# yarns_v03.net
KiCad netlist of a schematic drawn in EAGLE
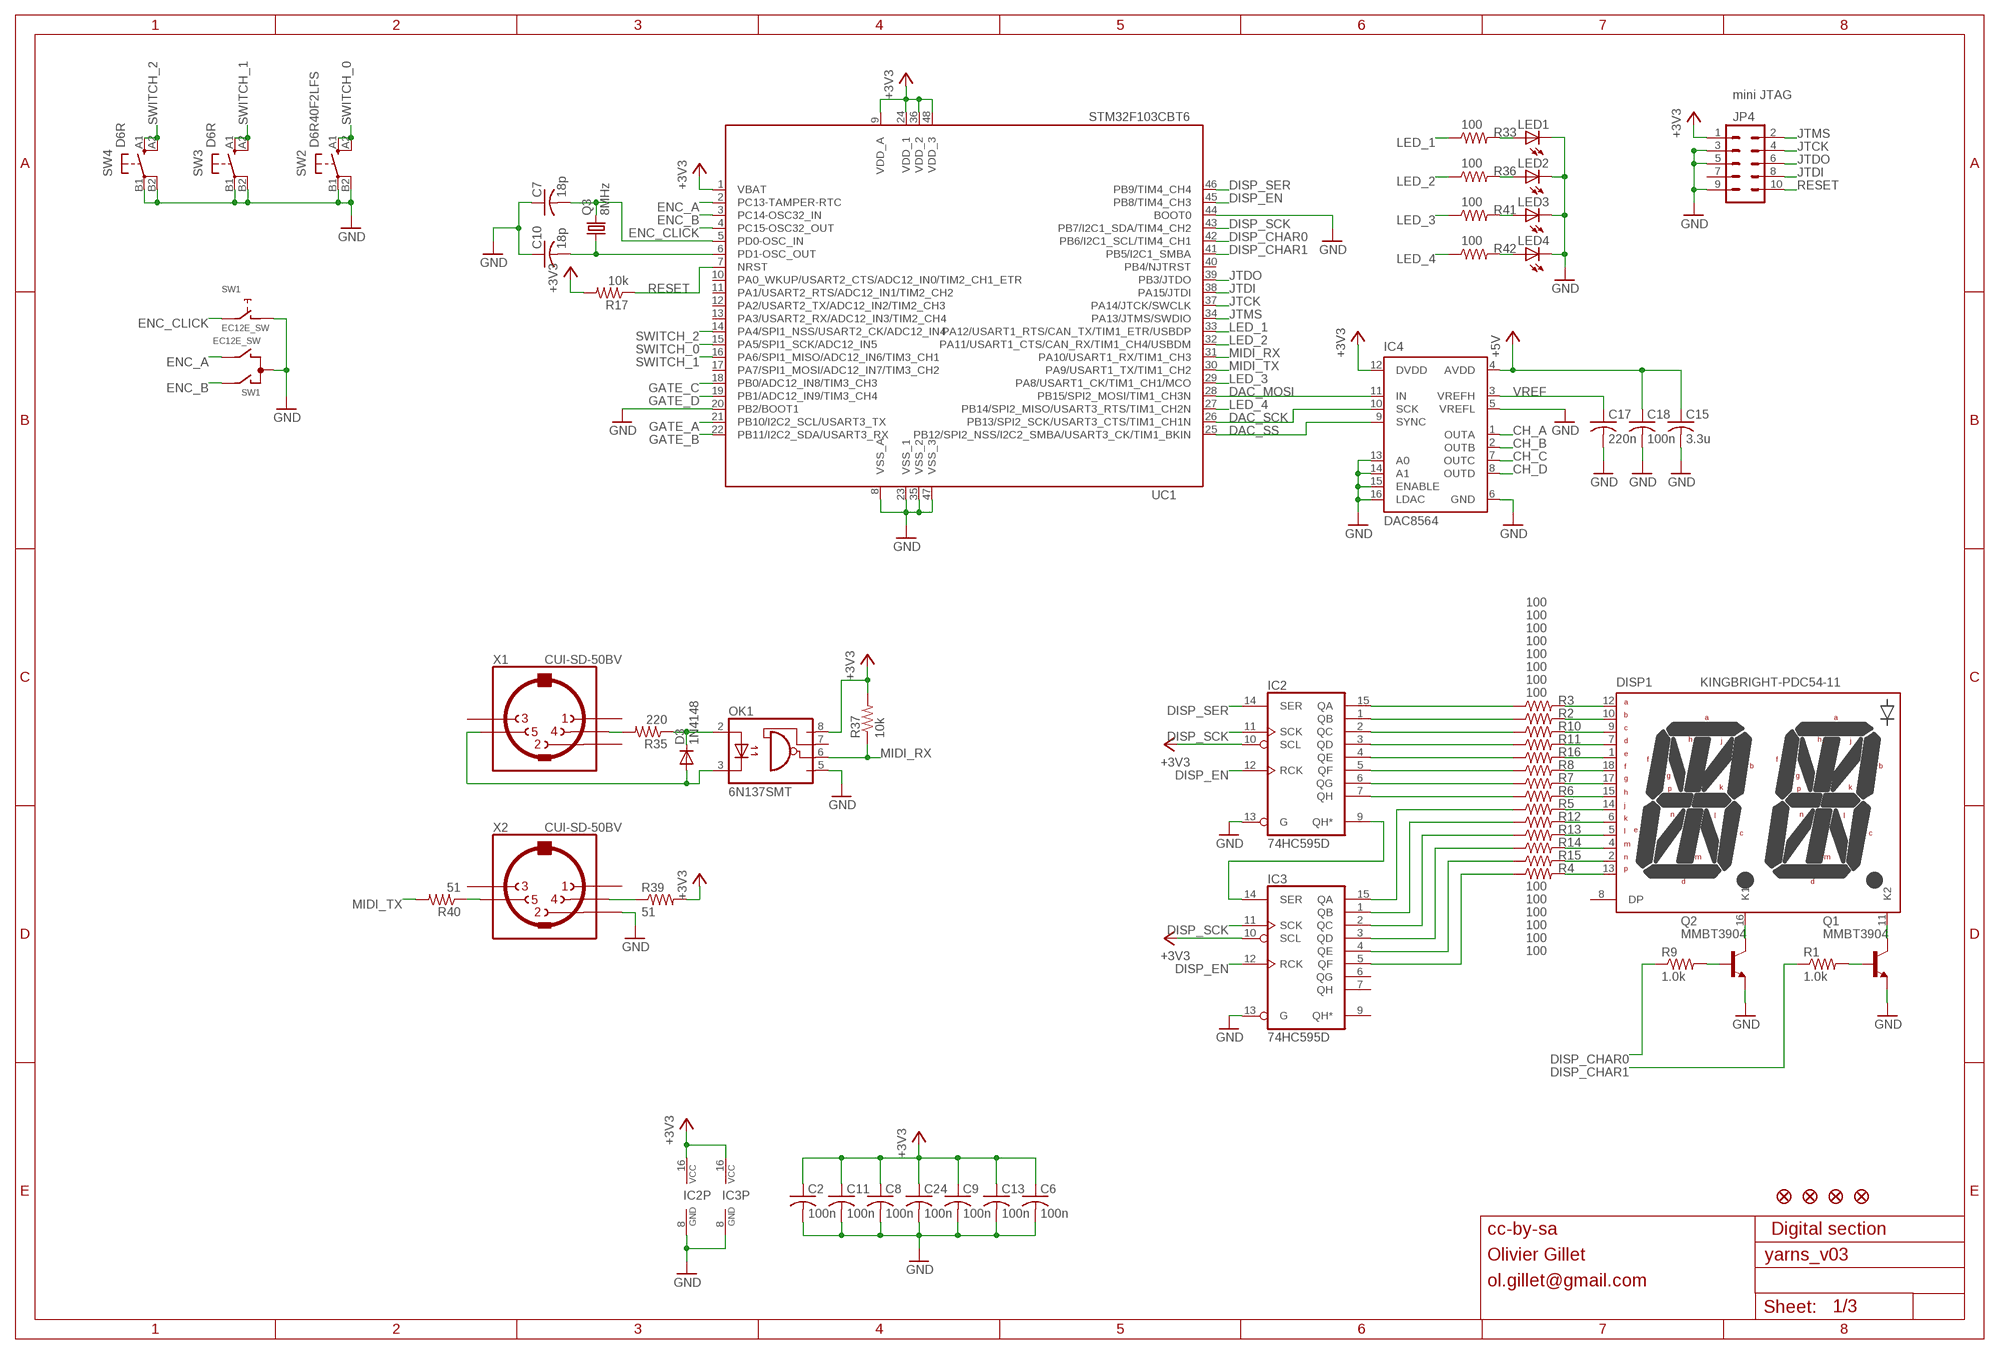
[diagram p0: schematic, sheet 1]
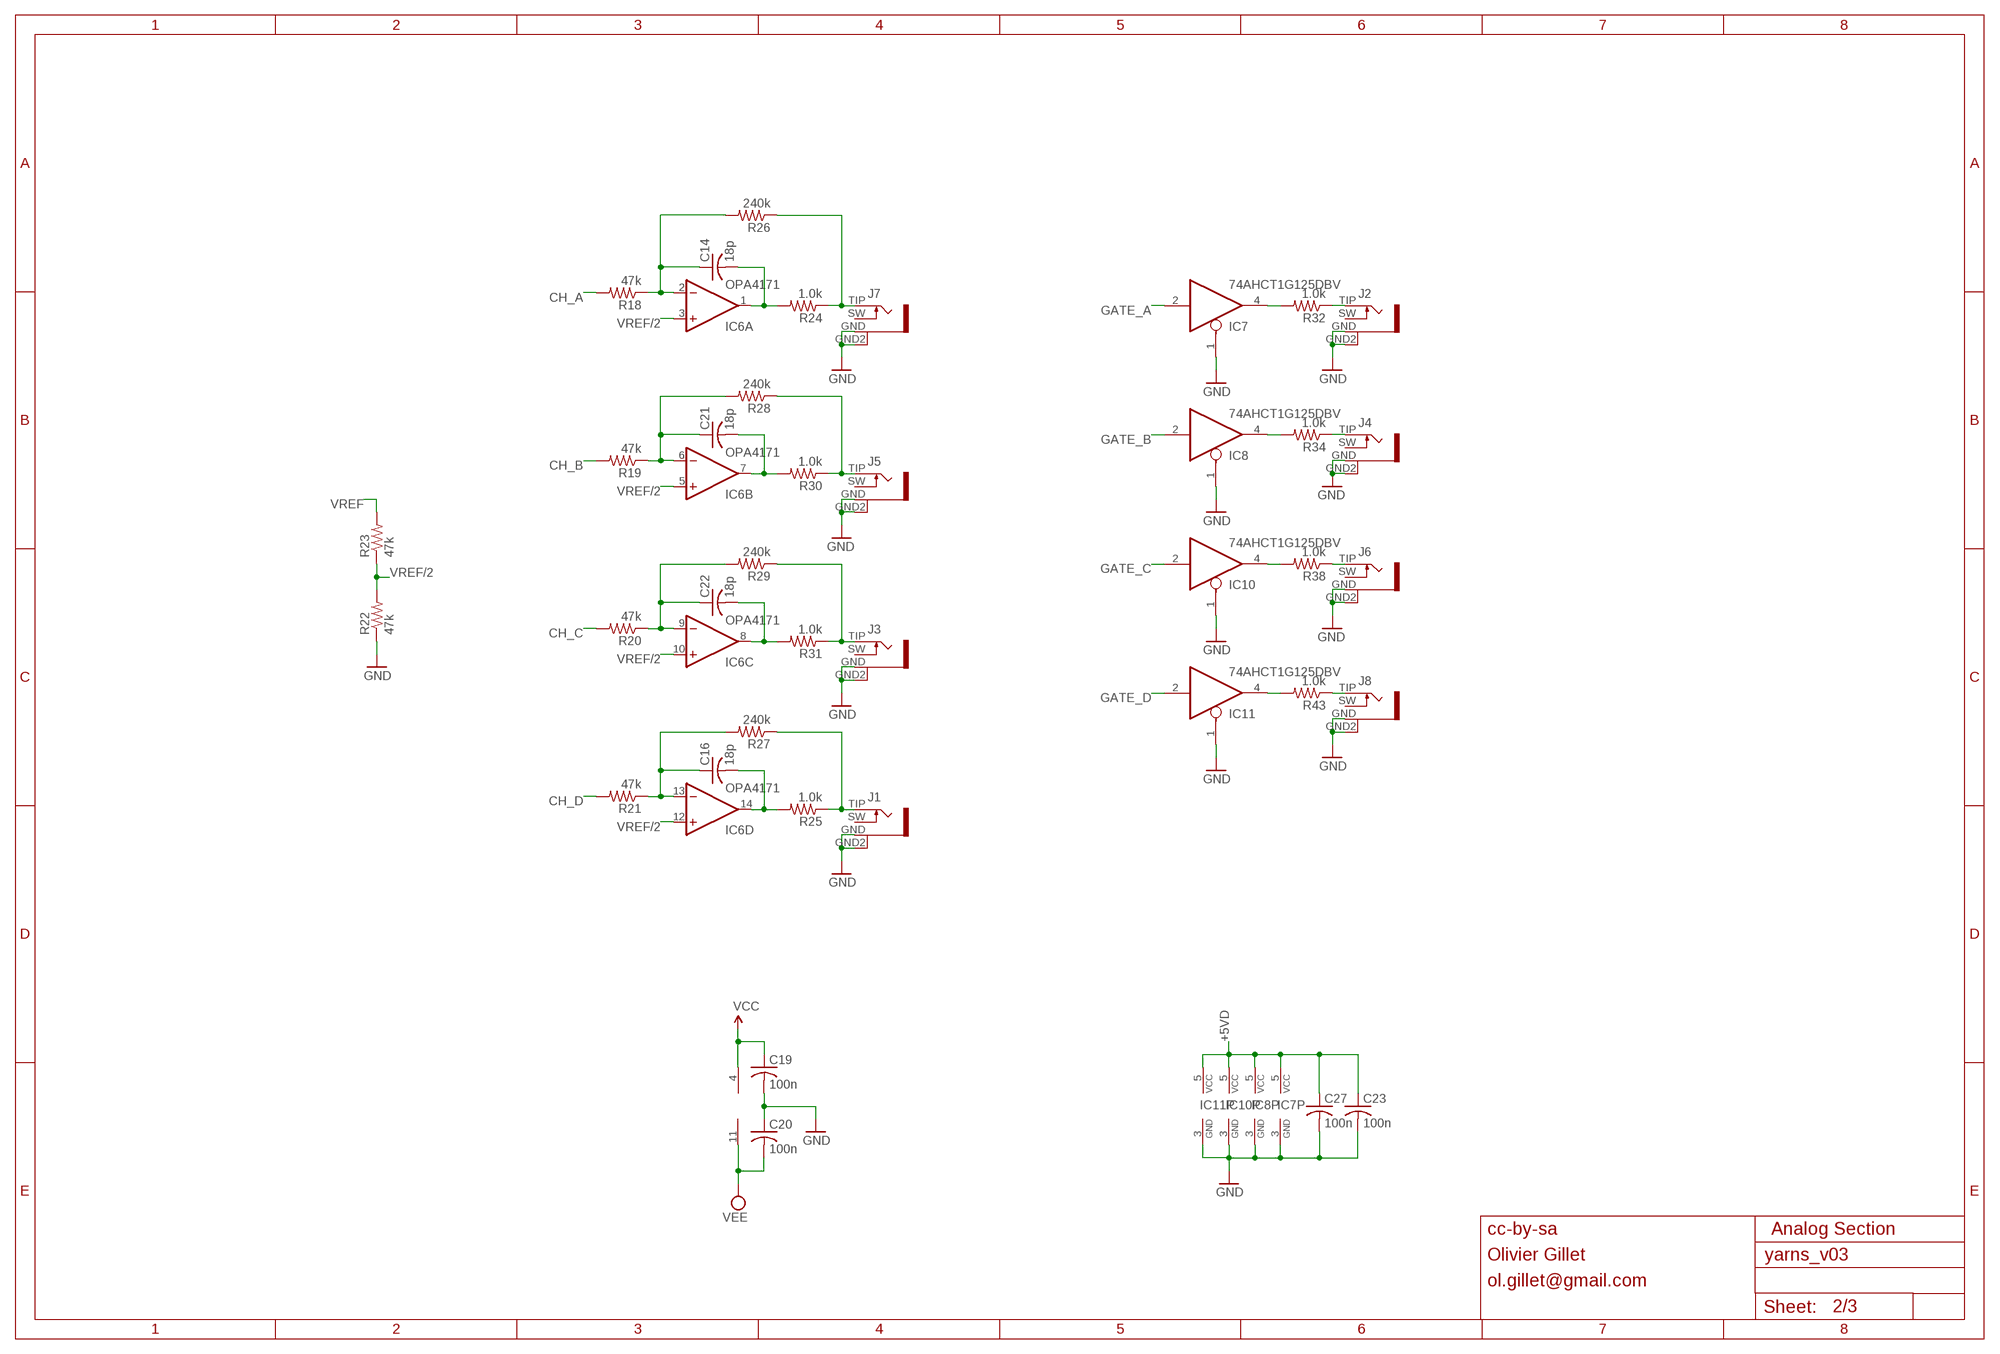
[diagram p1: schematic, sheet 2]
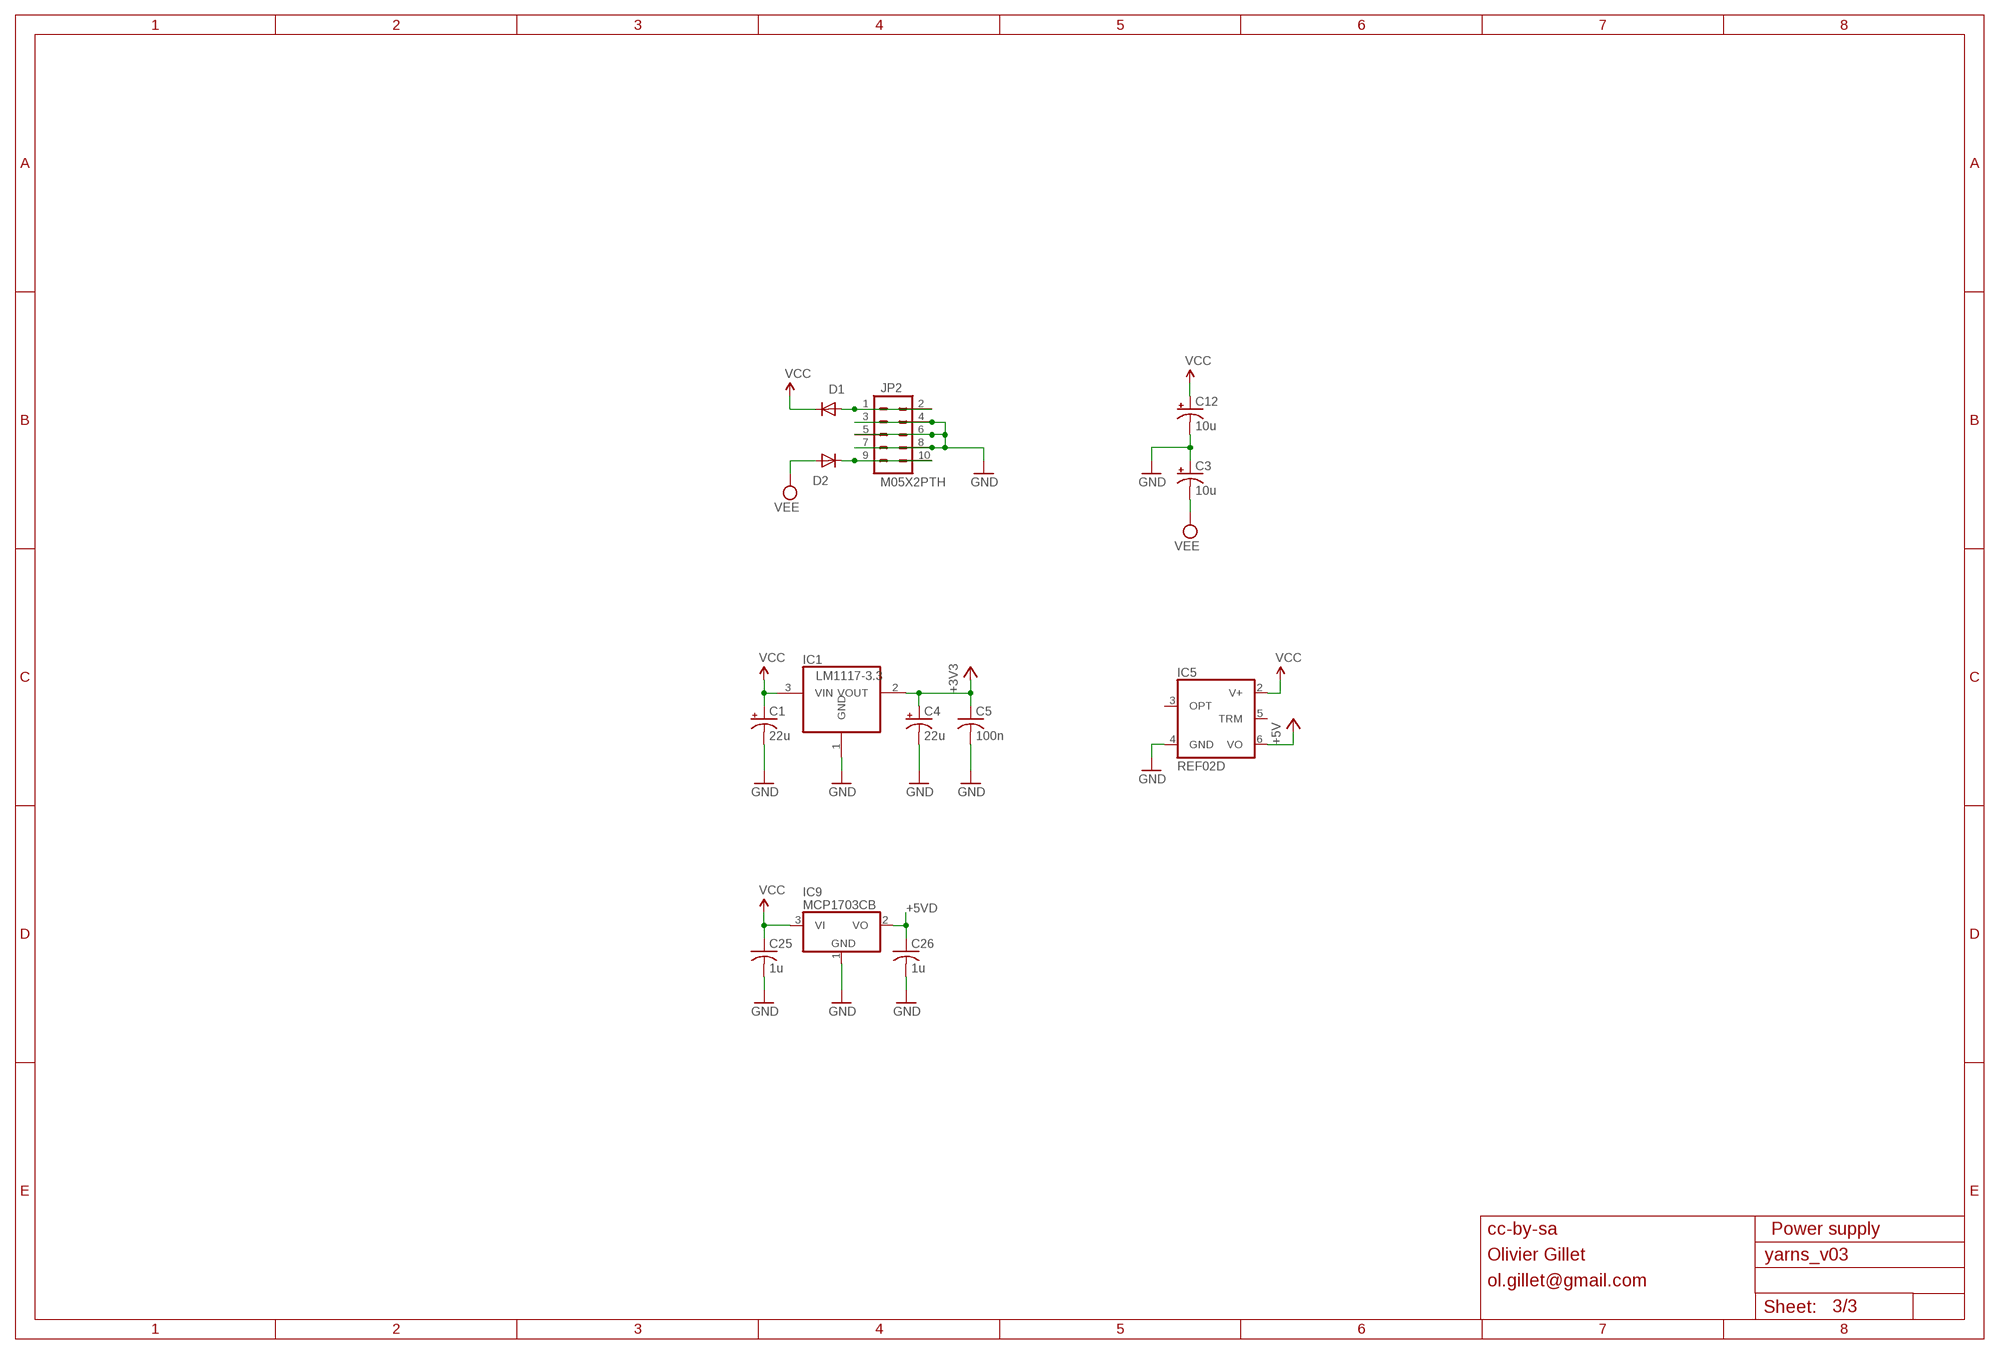
[diagram p2: schematic, sheet 3]

(export (version "E")
  (design (tool "Eeschema 10.0.6"))
  (components
    (comp (ref "C1")
      (value "22u")
      (footprint "eagle-import:PANASONIC_C")
      (libsource (lib "eagle-import") (part "CPOL-USC"))
    )
    (comp (ref "C3")
      (value "10u")
      (footprint "eagle-import:PANASONIC_A")
      (libsource (lib "eagle-import") (part "CPOL-USA"))
    )
    (comp (ref "C4")
      (value "22u")
      (footprint "eagle-import:PANASONIC_C")
      (libsource (lib "eagle-import") (part "CPOL-USC"))
    )
    (comp (ref "C5")
      (value "100n")
      (footprint "eagle-import:C0603")
      (libsource (lib "eagle-import") (part "C-USC0603"))
    )
    (comp (ref "C12")
      (value "10u")
      (footprint "eagle-import:PANASONIC_A")
      (libsource (lib "eagle-import") (part "CPOL-USA"))
    )
    (comp (ref "C25")
      (value "1u")
      (footprint "eagle-import:C0603")
      (libsource (lib "eagle-import") (part "C-USC0603"))
    )
    (comp (ref "C26")
      (value "1u")
      (footprint "eagle-import:C0603")
      (libsource (lib "eagle-import") (part "C-USC0603"))
    )
    (comp (ref "D1")
      (value "1N5819HW")
      (footprint "eagle-import:SOD123")
      (libsource (lib "eagle-import") (part "DIODE-SOD123"))
    )
    (comp (ref "D2")
      (value "1N5819HW")
      (footprint "eagle-import:SOD123")
      (libsource (lib "eagle-import") (part "DIODE-SOD123"))
    )
    (comp (ref "IC1")
      (value "LM1117-3.3")
      (footprint "eagle-import:SOT223")
      (libsource (lib "eagle-import") (part "REG1117"))
    )
    (comp (ref "IC5")
      (value "REF02D")
      (footprint "eagle-import:SO08")
      (libsource (lib "eagle-import") (part "REF02D"))
    )
    (comp (ref "IC9")
      (value "MCP1703CB")
      (footprint "eagle-import:SOT23")
      (libsource (lib "eagle-import") (part "MCP1703CB"))
    )
    (comp (ref "JP2")
      (value "M05X2PTH")
      (footprint "eagle-import:AVR_ICSP")
      (libsource (lib "eagle-import") (part "M05X2PTH"))
    )
    (comp (ref "C14")
      (value "18p")
      (footprint "eagle-import:C0603")
      (libsource (lib "eagle-import") (part "C-USC0603"))
    )
    (comp (ref "C16")
      (value "18p")
      (footprint "eagle-import:C0603")
      (libsource (lib "eagle-import") (part "C-USC0603"))
    )
    (comp (ref "C19")
      (value "100n")
      (footprint "eagle-import:C0603")
      (libsource (lib "eagle-import") (part "C-USC0603"))
    )
    (comp (ref "C20")
      (value "100n")
      (footprint "eagle-import:C0603")
      (libsource (lib "eagle-import") (part "C-USC0603"))
    )
    (comp (ref "C21")
      (value "18p")
      (footprint "eagle-import:C0603")
      (libsource (lib "eagle-import") (part "C-USC0603"))
    )
    (comp (ref "C22")
      (value "18p")
      (footprint "eagle-import:C0603")
      (libsource (lib "eagle-import") (part "C-USC0603"))
    )
    (comp (ref "C23")
      (value "100n")
      (footprint "eagle-import:C0603")
      (libsource (lib "eagle-import") (part "C-USC0603"))
    )
    (comp (ref "C27")
      (value "100n")
      (footprint "eagle-import:C0603")
      (libsource (lib "eagle-import") (part "C-USC0603"))
    )
    (comp (ref "IC6")
      (value "OPA4171")
      (footprint "eagle-import:SO14")
      (libsource (lib "eagle-import") (part "TL074D"))
    )
    (comp (ref "IC7")
      (value "74AHCT1G125DBV")
      (footprint "eagle-import:SOT23-5")
      (libsource (lib "eagle-import") (part "741G125DBVAHCT"))
    )
    (comp (ref "IC8")
      (value "74AHCT1G125DBV")
      (footprint "eagle-import:SOT23-5")
      (libsource (lib "eagle-import") (part "741G125DBVAHCT"))
    )
    (comp (ref "IC10")
      (value "74AHCT1G125DBV")
      (footprint "eagle-import:SOT23-5")
      (libsource (lib "eagle-import") (part "741G125DBVAHCT"))
    )
    (comp (ref "IC11")
      (value "74AHCT1G125DBV")
      (footprint "eagle-import:SOT23-5")
      (libsource (lib "eagle-import") (part "741G125DBVAHCT"))
    )
    (comp (ref "J1")
      (value "PJ301WQP")
      (footprint "eagle-import:WQP_PJ_301BM")
      (libsource (lib "eagle-import") (part "PJ301WQP"))
    )
    (comp (ref "J2")
      (value "PJ301WQP")
      (footprint "eagle-import:WQP_PJ_301BM")
      (libsource (lib "eagle-import") (part "PJ301WQP"))
    )
    (comp (ref "J3")
      (value "PJ301WQP")
      (footprint "eagle-import:WQP_PJ_301BM")
      (libsource (lib "eagle-import") (part "PJ301WQP"))
    )
    (comp (ref "J4")
      (value "PJ301WQP")
      (footprint "eagle-import:WQP_PJ_301BM")
      (libsource (lib "eagle-import") (part "PJ301WQP"))
    )
    (comp (ref "J5")
      (value "PJ301WQP")
      (footprint "eagle-import:WQP_PJ_301BM")
      (libsource (lib "eagle-import") (part "PJ301WQP"))
    )
    (comp (ref "J6")
      (value "PJ301WQP")
      (footprint "eagle-import:WQP_PJ_301BM")
      (libsource (lib "eagle-import") (part "PJ301WQP"))
    )
    (comp (ref "J7")
      (value "PJ301WQP")
      (footprint "eagle-import:WQP_PJ_301BM")
      (libsource (lib "eagle-import") (part "PJ301WQP"))
    )
    (comp (ref "J8")
      (value "PJ301WQP")
      (footprint "eagle-import:WQP_PJ_301BM")
      (libsource (lib "eagle-import") (part "PJ301WQP"))
    )
    (comp (ref "R18")
      (value "47k")
      (footprint "eagle-import:R0603")
      (libsource (lib "eagle-import") (part "R-US_R0603"))
    )
    (comp (ref "R19")
      (value "47k")
      (footprint "eagle-import:R0603")
      (libsource (lib "eagle-import") (part "R-US_R0603"))
    )
    (comp (ref "R20")
      (value "47k")
      (footprint "eagle-import:R0603")
      (libsource (lib "eagle-import") (part "R-US_R0603"))
    )
    (comp (ref "R21")
      (value "47k")
      (footprint "eagle-import:R0603")
      (libsource (lib "eagle-import") (part "R-US_R0603"))
    )
    (comp (ref "R22")
      (value "47k")
      (footprint "eagle-import:R0603")
      (libsource (lib "eagle-import") (part "R-US_R0603"))
    )
    (comp (ref "R23")
      (value "47k")
      (footprint "eagle-import:R0603")
      (libsource (lib "eagle-import") (part "R-US_R0603"))
    )
    (comp (ref "R24")
      (value "1.0k")
      (footprint "eagle-import:R0603")
      (libsource (lib "eagle-import") (part "R-US_R0603"))
    )
    (comp (ref "R25")
      (value "1.0k")
      (footprint "eagle-import:R0603")
      (libsource (lib "eagle-import") (part "R-US_R0603"))
    )
    (comp (ref "R26")
      (value "240k")
      (footprint "eagle-import:R0603")
      (libsource (lib "eagle-import") (part "R-US_R0603"))
    )
    (comp (ref "R27")
      (value "240k")
      (footprint "eagle-import:R0603")
      (libsource (lib "eagle-import") (part "R-US_R0603"))
    )
    (comp (ref "R28")
      (value "240k")
      (footprint "eagle-import:R0603")
      (libsource (lib "eagle-import") (part "R-US_R0603"))
    )
    (comp (ref "R29")
      (value "240k")
      (footprint "eagle-import:R0603")
      (libsource (lib "eagle-import") (part "R-US_R0603"))
    )
    (comp (ref "R30")
      (value "1.0k")
      (footprint "eagle-import:R0603")
      (libsource (lib "eagle-import") (part "R-US_R0603"))
    )
    (comp (ref "R31")
      (value "1.0k")
      (footprint "eagle-import:R0603")
      (libsource (lib "eagle-import") (part "R-US_R0603"))
    )
    (comp (ref "R32")
      (value "1.0k")
      (footprint "eagle-import:R0603")
      (libsource (lib "eagle-import") (part "R-US_R0603"))
    )
    (comp (ref "R34")
      (value "1.0k")
      (footprint "eagle-import:R0603")
      (libsource (lib "eagle-import") (part "R-US_R0603"))
    )
    (comp (ref "R38")
      (value "1.0k")
      (footprint "eagle-import:R0603")
      (libsource (lib "eagle-import") (part "R-US_R0603"))
    )
    (comp (ref "R43")
      (value "1.0k")
      (footprint "eagle-import:R0603")
      (libsource (lib "eagle-import") (part "R-US_R0603"))
    )
    (comp (ref "C2")
      (value "100n")
      (footprint "eagle-import:C0603")
      (libsource (lib "eagle-import") (part "C-USC0603"))
    )
    (comp (ref "C6")
      (value "100n")
      (footprint "eagle-import:C0603")
      (libsource (lib "eagle-import") (part "C-USC0603"))
    )
    (comp (ref "C7")
      (value "18p")
      (footprint "eagle-import:C0603")
      (libsource (lib "eagle-import") (part "C-USC0603"))
    )
    (comp (ref "C8")
      (value "100n")
      (footprint "eagle-import:C0603")
      (libsource (lib "eagle-import") (part "C-USC0603"))
    )
    (comp (ref "C9")
      (value "100n")
      (footprint "eagle-import:C0603")
      (libsource (lib "eagle-import") (part "C-USC0603"))
    )
    (comp (ref "C10")
      (value "18p")
      (footprint "eagle-import:C0603")
      (libsource (lib "eagle-import") (part "C-USC0603"))
    )
    (comp (ref "C11")
      (value "100n")
      (footprint "eagle-import:C0603")
      (libsource (lib "eagle-import") (part "C-USC0603"))
    )
    (comp (ref "C13")
      (value "100n")
      (footprint "eagle-import:C0603")
      (libsource (lib "eagle-import") (part "C-USC0603"))
    )
    (comp (ref "C15")
      (value "3.3u")
      (footprint "eagle-import:C0603")
      (libsource (lib "eagle-import") (part "C-USC0603"))
    )
    (comp (ref "C17")
      (value "220n")
      (footprint "eagle-import:C0603")
      (libsource (lib "eagle-import") (part "C-USC0603"))
    )
    (comp (ref "C18")
      (value "100n")
      (footprint "eagle-import:C0603")
      (libsource (lib "eagle-import") (part "C-USC0603"))
    )
    (comp (ref "C24")
      (value "100n")
      (footprint "eagle-import:C0603")
      (libsource (lib "eagle-import") (part "C-USC0603"))
    )
    (comp (ref "D3")
      (value "1N4148")
      (footprint "eagle-import:SOD323-W")
      (libsource (lib "eagle-import") (part "DIODE-SOD323-W"))
    )
    (comp (ref "DISP1")
      (value "KINGBRIGHT-PDC54-11")
      (footprint "eagle-import:PDC54")
      (libsource (lib "eagle-import") (part "KINGBRIGHT-PDC54-11"))
    )
    (comp (ref "F1")
      (value "FIDUCIAL1X2")
      (footprint "eagle-import:FIDUCIAL-1X2")
      (libsource (lib "eagle-import") (part "FIDUCIAL1X2"))
    )
    (comp (ref "F3")
      (value "FIDUCIAL1X2")
      (footprint "eagle-import:FIDUCIAL-1X2")
      (libsource (lib "eagle-import") (part "FIDUCIAL1X2"))
    )
    (comp (ref "F5")
      (value "FIDUCIAL1X2")
      (footprint "eagle-import:FIDUCIAL-1X2")
      (libsource (lib "eagle-import") (part "FIDUCIAL1X2"))
    )
    (comp (ref "F6")
      (value "FIDUCIAL1X2")
      (footprint "eagle-import:FIDUCIAL-1X2")
      (libsource (lib "eagle-import") (part "FIDUCIAL1X2"))
    )
    (comp (ref "IC2")
      (value "74HC595D")
      (footprint "eagle-import:SO16")
      (libsource (lib "eagle-import") (part "74595DHC"))
    )
    (comp (ref "IC3")
      (value "74HC595D")
      (footprint "eagle-import:SO16")
      (libsource (lib "eagle-import") (part "74595DHC"))
    )
    (comp (ref "IC4")
      (value "DAC8564")
      (footprint "eagle-import:SOP65P640X110-16N")
      (libsource (lib "eagle-import") (part "DAC8564"))
    )
    (comp (ref "JP4")
      (value "M05X2MINIJTAG")
      (footprint "eagle-import:2X5-1.27")
      (libsource (lib "eagle-import") (part "M05X2MINIJTAG"))
    )
    (comp (ref "LED1")
      (value "LED3MM")
      (footprint "eagle-import:LED3MM")
      (libsource (lib "eagle-import") (part "LED3MM"))
    )
    (comp (ref "LED2")
      (value "LED3MM")
      (footprint "eagle-import:LED3MM")
      (libsource (lib "eagle-import") (part "LED3MM"))
    )
    (comp (ref "LED3")
      (value "LED3MM")
      (footprint "eagle-import:LED3MM")
      (libsource (lib "eagle-import") (part "LED3MM"))
    )
    (comp (ref "LED4")
      (value "LED3MM")
      (footprint "eagle-import:LED3MM")
      (libsource (lib "eagle-import") (part "LED3MM"))
    )
    (comp (ref "OK1")
      (value "6N137SMT")
      (footprint "eagle-import:DIL8-SMD")
      (libsource (lib "eagle-import") (part "6N137SMT"))
    )
    (comp (ref "Q1")
      (value "MMBT3904")
      (footprint "eagle-import:SOT23-BEC")
      (libsource (lib "eagle-import") (part "-NPN-SOT23-BECMMBT3904LT1"))
    )
    (comp (ref "Q2")
      (value "MMBT3904")
      (footprint "eagle-import:SOT23-BEC")
      (libsource (lib "eagle-import") (part "-NPN-SOT23-BECMMBT3904LT1"))
    )
    (comp (ref "Q3")
      (value "8MHz")
      (footprint "eagle-import:HC49UP")
      (libsource (lib "eagle-import") (part "CRYSTALHC49UP"))
    )
    (comp (ref "R1")
      (value "1.0k")
      (footprint "eagle-import:R0603")
      (libsource (lib "eagle-import") (part "R-US_R0603"))
    )
    (comp (ref "R2")
      (value "100")
      (footprint "eagle-import:R0603")
      (libsource (lib "eagle-import") (part "R-US_R0603"))
    )
    (comp (ref "R3")
      (value "100")
      (footprint "eagle-import:R0603")
      (libsource (lib "eagle-import") (part "R-US_R0603"))
    )
    (comp (ref "R4")
      (value "100")
      (footprint "eagle-import:R0603")
      (libsource (lib "eagle-import") (part "R-US_R0603"))
    )
    (comp (ref "R5")
      (value "100")
      (footprint "eagle-import:R0603")
      (libsource (lib "eagle-import") (part "R-US_R0603"))
    )
    (comp (ref "R6")
      (value "100")
      (footprint "eagle-import:R0603")
      (libsource (lib "eagle-import") (part "R-US_R0603"))
    )
    (comp (ref "R7")
      (value "100")
      (footprint "eagle-import:R0603")
      (libsource (lib "eagle-import") (part "R-US_R0603"))
    )
    (comp (ref "R8")
      (value "100")
      (footprint "eagle-import:R0603")
      (libsource (lib "eagle-import") (part "R-US_R0603"))
    )
    (comp (ref "R9")
      (value "1.0k")
      (footprint "eagle-import:R0603")
      (libsource (lib "eagle-import") (part "R-US_R0603"))
    )
    (comp (ref "R10")
      (value "100")
      (footprint "eagle-import:R0603")
      (libsource (lib "eagle-import") (part "R-US_R0603"))
    )
    (comp (ref "R11")
      (value "100")
      (footprint "eagle-import:R0603")
      (libsource (lib "eagle-import") (part "R-US_R0603"))
    )
    (comp (ref "R12")
      (value "100")
      (footprint "eagle-import:R0603")
      (libsource (lib "eagle-import") (part "R-US_R0603"))
    )
    (comp (ref "R13")
      (value "100")
      (footprint "eagle-import:R0603")
      (libsource (lib "eagle-import") (part "R-US_R0603"))
    )
    (comp (ref "R14")
      (value "100")
      (footprint "eagle-import:R0603")
      (libsource (lib "eagle-import") (part "R-US_R0603"))
    )
    (comp (ref "R15")
      (value "100")
      (footprint "eagle-import:R0603")
      (libsource (lib "eagle-import") (part "R-US_R0603"))
    )
    (comp (ref "R16")
      (value "100")
      (footprint "eagle-import:R0603")
      (libsource (lib "eagle-import") (part "R-US_R0603"))
    )
    (comp (ref "R17")
      (value "10k")
      (footprint "eagle-import:R0603")
      (libsource (lib "eagle-import") (part "R-US_R0603"))
    )
    (comp (ref "R33")
      (value "100")
      (footprint "eagle-import:R0603")
      (libsource (lib "eagle-import") (part "R-US_R0603"))
    )
    (comp (ref "R35")
      (value "220")
      (footprint "eagle-import:R0603")
      (libsource (lib "eagle-import") (part "R-US_R0603"))
    )
    (comp (ref "R36")
      (value "100")
      (footprint "eagle-import:R0603")
      (libsource (lib "eagle-import") (part "R-US_R0603"))
    )
    (comp (ref "R37")
      (value "10k")
      (footprint "eagle-import:R0603")
      (libsource (lib "eagle-import") (part "R-US_R0603"))
    )
    (comp (ref "R39")
      (value "51")
      (footprint "eagle-import:R0603")
      (libsource (lib "eagle-import") (part "R-US_R0603"))
    )
    (comp (ref "R40")
      (value "51")
      (footprint "eagle-import:R0603")
      (libsource (lib "eagle-import") (part "R-US_R0603"))
    )
    (comp (ref "R41")
      (value "100")
      (footprint "eagle-import:R0603")
      (libsource (lib "eagle-import") (part "R-US_R0603"))
    )
    (comp (ref "R42")
      (value "100")
      (footprint "eagle-import:R0603")
      (libsource (lib "eagle-import") (part "R-US_R0603"))
    )
    (comp (ref "SW1")
      (value "EC12E_SW")
      (footprint "eagle-import:ALPS_EC12E_SW")
      (libsource (lib "eagle-import") (part "EC12E_SW"))
    )
    (comp (ref "SW2")
      (value "D6R40F2LFS")
      (footprint "eagle-import:D6R")
      (libsource (lib "eagle-import") (part "D6R"))
    )
    (comp (ref "SW3")
      (value "D6R")
      (footprint "eagle-import:D6R")
      (libsource (lib "eagle-import") (part "D6R"))
    )
    (comp (ref "SW4")
      (value "D6R")
      (footprint "eagle-import:D6R")
      (libsource (lib "eagle-import") (part "D6R"))
    )
    (comp (ref "UC1")
      (value "STM32F103CBT6")
      (footprint "eagle-import:LQFP48")
      (libsource (lib "eagle-import") (part "STM32F103CB"))
    )
    (comp (ref "X1")
      (value "CUI-SD-50BV")
      (footprint "eagle-import:SD-50BV")
      (libsource (lib "eagle-import") (part "MAB5SHCUI-SD-50BV"))
    )
    (comp (ref "X2")
      (value "CUI-SD-50BV")
      (footprint "eagle-import:SD-50BV")
      (libsource (lib "eagle-import") (part "MAB5SHCUI-SD-50BV"))
    )
  )
  (nets
    (net (code "1") (name "+3V3") (class "Default")
      (node (ref "C11") (pin "1") (pinfunction "1_1") (pintype "passive"))
      (node (ref "C13") (pin "1") (pinfunction "1_1") (pintype "passive"))
      (node (ref "C2") (pin "1") (pinfunction "1_1") (pintype "passive"))
      (node (ref "C24") (pin "1") (pinfunction "1_1") (pintype "passive"))
      (node (ref "C4") (pin "+") (pinfunction "+_+") (pintype "passive"))
      (node (ref "C5") (pin "1") (pinfunction "1_1") (pintype "passive"))
      (node (ref "C6") (pin "1") (pinfunction "1_1") (pintype "passive"))
      (node (ref "C8") (pin "1") (pinfunction "1_1") (pintype "passive"))
      (node (ref "C9") (pin "1") (pinfunction "1_1") (pintype "passive"))
      (node (ref "IC1") (pin "2") (pinfunction "VOUT_2") (pintype "output"))
      (node (ref "IC2") (pin "10") (pinfunction "SCL_10") (pintype "input"))
      (node (ref "IC2") (pin "16") (pinfunction "VCC_16") (pintype "power_in"))
      (node (ref "IC3") (pin "10") (pinfunction "SCL_10") (pintype "input"))
      (node (ref "IC3") (pin "16") (pinfunction "VCC_16") (pintype "power_in"))
      (node (ref "IC4") (pin "12") (pinfunction "DVDD_12") (pintype "power_in"))
      (node (ref "JP4") (pin "1") (pinfunction "1_1") (pintype "passive"))
      (node (ref "OK1") (pin "8") (pinfunction "VCC_8") (pintype "passive"))
      (node (ref "R17") (pin "2") (pinfunction "2_2") (pintype "passive"))
      (node (ref "R37") (pin "2") (pinfunction "2_2") (pintype "passive"))
      (node (ref "R39") (pin "2") (pinfunction "2_2") (pintype "passive"))
      (node (ref "UC1") (pin "1") (pinfunction "VBAT_1") (pintype "power_in"))
      (node (ref "UC1") (pin "24") (pinfunction "VDD_1_24") (pintype "power_in"))
      (node (ref "UC1") (pin "36") (pinfunction "VDD_2_36") (pintype "power_in"))
      (node (ref "UC1") (pin "48") (pinfunction "VDD_3_48") (pintype "power_in"))
      (node (ref "UC1") (pin "9") (pinfunction "VDD_A_9") (pintype "power_in"))
    )
    (net (code "2") (name "+5V") (class "Default")
      (node (ref "C15") (pin "1") (pinfunction "1_1") (pintype "passive"))
      (node (ref "C18") (pin "1") (pinfunction "1_1") (pintype "passive"))
      (node (ref "IC4") (pin "4") (pinfunction "AVDD_4") (pintype "power_in"))
      (node (ref "IC5") (pin "6") (pinfunction "VO_6") (pintype "output"))
    )
    (net (code "3") (name "+5VD") (class "Default")
      (node (ref "C23") (pin "1") (pinfunction "1_1") (pintype "passive"))
      (node (ref "C26") (pin "1") (pinfunction "1_1") (pintype "passive"))
      (node (ref "C27") (pin "1") (pinfunction "1_1") (pintype "passive"))
      (node (ref "IC10") (pin "5") (pinfunction "VCC_5") (pintype "power_in"))
      (node (ref "IC11") (pin "5") (pinfunction "VCC_5") (pintype "power_in"))
      (node (ref "IC7") (pin "5") (pinfunction "VCC_5") (pintype "power_in"))
      (node (ref "IC8") (pin "5") (pinfunction "VCC_5") (pintype "power_in"))
      (node (ref "IC9") (pin "2") (pinfunction "VO_2") (pintype "passive"))
    )
    (net (code "4") (name "CH_A") (class "Default")
      (node (ref "IC4") (pin "1") (pinfunction "OUTA_1") (pintype "output"))
      (node (ref "R18") (pin "2") (pinfunction "2_2") (pintype "passive"))
    )
    (net (code "5") (name "CH_B") (class "Default")
      (node (ref "IC4") (pin "2") (pinfunction "OUTB_2") (pintype "output"))
      (node (ref "R19") (pin "2") (pinfunction "2_2") (pintype "passive"))
    )
    (net (code "6") (name "CH_C") (class "Default")
      (node (ref "IC4") (pin "7") (pinfunction "OUTC_7") (pintype "output"))
      (node (ref "R20") (pin "2") (pinfunction "2_2") (pintype "passive"))
    )
    (net (code "7") (name "CH_D") (class "Default")
      (node (ref "IC4") (pin "8") (pinfunction "OUTD_8") (pintype "output"))
      (node (ref "R21") (pin "2") (pinfunction "2_2") (pintype "passive"))
    )
    (net (code "8") (name "DAC_MOSI") (class "Default")
      (node (ref "IC4") (pin "11") (pinfunction "IN_11") (pintype "input"))
      (node (ref "UC1") (pin "28") (pinfunction "PB15/SPI2_MOSI/TIM1_CH3N_28") (pintype "input"))
    )
    (net (code "9") (name "DAC_SCK") (class "Default")
      (node (ref "IC4") (pin "10") (pinfunction "SCK_10") (pintype "input"))
      (node (ref "UC1") (pin "26") (pinfunction "PB13/SPI2_SCK/USART3_CTS/TIM1_CH1N_26") (pintype "input"))
    )
    (net (code "10") (name "DAC_SS") (class "Default")
      (node (ref "IC4") (pin "9") (pinfunction "SYNC_9") (pintype "input"))
      (node (ref "UC1") (pin "25") (pinfunction "PB12/SPI2_NSS/I2C2_SMBA/USART3_CK/TIM1_BKIN_25") (pintype "input"))
    )
    (net (code "11") (name "DISP_CHAR0") (class "Default")
      (node (ref "R9") (pin "1") (pinfunction "1_1") (pintype "passive"))
      (node (ref "UC1") (pin "42") (pinfunction "PB6/I2C1_SCL/TIM4_CH1_42") (pintype "input"))
    )
    (net (code "12") (name "DISP_CHAR1") (class "Default")
      (node (ref "R1") (pin "1") (pinfunction "1_1") (pintype "passive"))
      (node (ref "UC1") (pin "41") (pinfunction "PB5/I2C1_SMBA_41") (pintype "input"))
    )
    (net (code "13") (name "DISP_EN") (class "Default")
      (node (ref "IC2") (pin "12") (pinfunction "RCK_12") (pintype "input"))
      (node (ref "IC3") (pin "12") (pinfunction "RCK_12") (pintype "input"))
      (node (ref "UC1") (pin "45") (pinfunction "PB8/TIM4_CH3_45") (pintype "bidirectional"))
    )
    (net (code "14") (name "DISP_SCK") (class "Default")
      (node (ref "IC2") (pin "11") (pinfunction "SCK_11") (pintype "input"))
      (node (ref "IC3") (pin "11") (pinfunction "SCK_11") (pintype "input"))
      (node (ref "UC1") (pin "43") (pinfunction "PB7/I2C1_SDA/TIM4_CH2_43") (pintype "bidirectional"))
    )
    (net (code "15") (name "DISP_SER") (class "Default")
      (node (ref "IC2") (pin "14") (pinfunction "SER_14") (pintype "input"))
      (node (ref "UC1") (pin "46") (pinfunction "PB9/TIM4_CH4_46") (pintype "input"))
    )
    (net (code "16") (name "ENC_A") (class "Default")
      (node (ref "SW1") (pin "B") (pinfunction "B_B") (pintype "passive"))
      (node (ref "UC1") (pin "2") (pinfunction "PC13-TAMPER-RTC_2") (pintype "input"))
    )
    (net (code "17") (name "ENC_B") (class "Default")
      (node (ref "SW1") (pin "A") (pinfunction "A_A") (pintype "passive"))
      (node (ref "UC1") (pin "3") (pinfunction "PC14-OSC32_IN_3") (pintype "input"))
    )
    (net (code "18") (name "ENC_CLICK") (class "Default")
      (node (ref "SW1") (pin "E") (pinfunction "2_E") (pintype "passive"))
      (node (ref "UC1") (pin "4") (pinfunction "PC15-OSC32_OUT_4") (pintype "input"))
    )
    (net (code "19") (name "GATE_A") (class "Default")
      (node (ref "IC7") (pin "2") (pinfunction "I_2") (pintype "input"))
      (node (ref "UC1") (pin "21") (pinfunction "PB10/I2C2_SCL/USART3_TX_21") (pintype "input"))
    )
    (net (code "20") (name "GATE_B") (class "Default")
      (node (ref "IC8") (pin "2") (pinfunction "I_2") (pintype "input"))
      (node (ref "UC1") (pin "22") (pinfunction "PB11/I2C2_SDA/USART3_RX_22") (pintype "input"))
    )
    (net (code "21") (name "GATE_C") (class "Default")
      (node (ref "IC10") (pin "2") (pinfunction "I_2") (pintype "input"))
      (node (ref "UC1") (pin "18") (pinfunction "PB0/ADC12_IN8/TIM3_CH3_18") (pintype "bidirectional"))
    )
    (net (code "22") (name "GATE_D") (class "Default")
      (node (ref "IC11") (pin "2") (pinfunction "I_2") (pintype "input"))
      (node (ref "UC1") (pin "19") (pinfunction "PB1/ADC12_IN9/TIM3_CH4_19") (pintype "bidirectional"))
    )
    (net (code "23") (name "GND") (class "Default")
      (node (ref "C1") (pin "-") (pinfunction "-_-") (pintype "passive"))
      (node (ref "C10") (pin "1") (pinfunction "1_1") (pintype "passive"))
      (node (ref "C11") (pin "2") (pinfunction "2_2") (pintype "passive"))
      (node (ref "C12") (pin "-") (pinfunction "-_-") (pintype "passive"))
      (node (ref "C13") (pin "2") (pinfunction "2_2") (pintype "passive"))
      (node (ref "C15") (pin "2") (pinfunction "2_2") (pintype "passive"))
      (node (ref "C17") (pin "2") (pinfunction "2_2") (pintype "passive"))
      (node (ref "C18") (pin "2") (pinfunction "2_2") (pintype "passive"))
      (node (ref "C19") (pin "2") (pinfunction "2_2") (pintype "passive"))
      (node (ref "C2") (pin "2") (pinfunction "2_2") (pintype "passive"))
      (node (ref "C20") (pin "1") (pinfunction "1_1") (pintype "passive"))
      (node (ref "C23") (pin "2") (pinfunction "2_2") (pintype "passive"))
      (node (ref "C24") (pin "2") (pinfunction "2_2") (pintype "passive"))
      (node (ref "C25") (pin "2") (pinfunction "2_2") (pintype "passive"))
      (node (ref "C26") (pin "2") (pinfunction "2_2") (pintype "passive"))
      (node (ref "C27") (pin "2") (pinfunction "2_2") (pintype "passive"))
      (node (ref "C3") (pin "+") (pinfunction "+_+") (pintype "passive"))
      (node (ref "C4") (pin "-") (pinfunction "-_-") (pintype "passive"))
      (node (ref "C5") (pin "2") (pinfunction "2_2") (pintype "passive"))
      (node (ref "C6") (pin "2") (pinfunction "2_2") (pintype "passive"))
      (node (ref "C7") (pin "1") (pinfunction "1_1") (pintype "passive"))
      (node (ref "C8") (pin "2") (pinfunction "2_2") (pintype "passive"))
      (node (ref "C9") (pin "2") (pinfunction "2_2") (pintype "passive"))
      (node (ref "IC1") (pin "1") (pinfunction "GND_1") (pintype "power_in"))
      (node (ref "IC10") (pin "1") (pinfunction "OE_1") (pintype "input"))
      (node (ref "IC10") (pin "3") (pinfunction "GND_3") (pintype "power_in"))
      (node (ref "IC11") (pin "1") (pinfunction "OE_1") (pintype "input"))
      (node (ref "IC11") (pin "3") (pinfunction "GND_3") (pintype "power_in"))
      (node (ref "IC2") (pin "13") (pinfunction "G_13") (pintype "input"))
      (node (ref "IC2") (pin "8") (pinfunction "GND_8") (pintype "power_in"))
      (node (ref "IC3") (pin "13") (pinfunction "G_13") (pintype "input"))
      (node (ref "IC3") (pin "8") (pinfunction "GND_8") (pintype "power_in"))
      (node (ref "IC4") (pin "13") (pinfunction "A0_13") (pintype "input"))
      (node (ref "IC4") (pin "14") (pinfunction "A1_14") (pintype "input"))
      (node (ref "IC4") (pin "15") (pinfunction "ENABLE_15") (pintype "input"))
      (node (ref "IC4") (pin "16") (pinfunction "LDAC_16") (pintype "input"))
      (node (ref "IC4") (pin "5") (pinfunction "VREFL_5") (pintype "bidirectional"))
      (node (ref "IC4") (pin "6") (pinfunction "GND_6") (pintype "power_in"))
      (node (ref "IC5") (pin "4") (pinfunction "GND_4") (pintype "power_in"))
      (node (ref "IC7") (pin "1") (pinfunction "OE_1") (pintype "input"))
      (node (ref "IC7") (pin "3") (pinfunction "GND_3") (pintype "power_in"))
      (node (ref "IC8") (pin "1") (pinfunction "OE_1") (pintype "input"))
      (node (ref "IC8") (pin "3") (pinfunction "GND_3") (pintype "power_in"))
      (node (ref "IC9") (pin "1") (pinfunction "GND_1") (pintype "passive"))
      (node (ref "J1") (pin "GND") (pinfunction "1_GND") (pintype "passive"))
      (node (ref "J1") (pin "GND2") (pinfunction "4_GND2") (pintype "passive"))
      (node (ref "J2") (pin "GND") (pinfunction "1_GND") (pintype "passive"))
      (node (ref "J2") (pin "GND2") (pinfunction "4_GND2") (pintype "passive"))
      (node (ref "J3") (pin "GND") (pinfunction "1_GND") (pintype "passive"))
      (node (ref "J3") (pin "GND2") (pinfunction "4_GND2") (pintype "passive"))
      (node (ref "J4") (pin "GND") (pinfunction "1_GND") (pintype "passive"))
      (node (ref "J4") (pin "GND2") (pinfunction "4_GND2") (pintype "passive"))
      (node (ref "J5") (pin "GND") (pinfunction "1_GND") (pintype "passive"))
      (node (ref "J5") (pin "GND2") (pinfunction "4_GND2") (pintype "passive"))
      (node (ref "J6") (pin "GND") (pinfunction "1_GND") (pintype "passive"))
      (node (ref "J6") (pin "GND2") (pinfunction "4_GND2") (pintype "passive"))
      (node (ref "J7") (pin "GND") (pinfunction "1_GND") (pintype "passive"))
      (node (ref "J7") (pin "GND2") (pinfunction "4_GND2") (pintype "passive"))
      (node (ref "J8") (pin "GND") (pinfunction "1_GND") (pintype "passive"))
      (node (ref "J8") (pin "GND2") (pinfunction "4_GND2") (pintype "passive"))
      (node (ref "JP2") (pin "3") (pinfunction "3_3") (pintype "passive"))
      (node (ref "JP2") (pin "4") (pinfunction "4_4") (pintype "passive"))
      (node (ref "JP2") (pin "5") (pinfunction "5_5") (pintype "passive"))
      (node (ref "JP2") (pin "6") (pinfunction "6_6") (pintype "passive"))
      (node (ref "JP2") (pin "7") (pinfunction "7_7") (pintype "passive"))
      (node (ref "JP2") (pin "8") (pinfunction "8_8") (pintype "passive"))
      (node (ref "JP4") (pin "3") (pinfunction "3_3") (pintype "passive"))
      (node (ref "JP4") (pin "5") (pinfunction "5_5") (pintype "passive"))
      (node (ref "JP4") (pin "9") (pinfunction "9_9") (pintype "passive"))
      (node (ref "LED1") (pin "K") (pinfunction "C_K") (pintype "passive"))
      (node (ref "LED2") (pin "K") (pinfunction "C_K") (pintype "passive"))
      (node (ref "LED3") (pin "K") (pinfunction "C_K") (pintype "passive"))
      (node (ref "LED4") (pin "K") (pinfunction "C_K") (pintype "passive"))
      (node (ref "OK1") (pin "5") (pinfunction "GND_5") (pintype "passive"))
      (node (ref "Q1") (pin "E") (pinfunction "E_E") (pintype "passive"))
      (node (ref "Q2") (pin "E") (pinfunction "E_E") (pintype "passive"))
      (node (ref "R22") (pin "1") (pinfunction "1_1") (pintype "passive"))
      (node (ref "SW1") (pin "C") (pinfunction "C_C") (pintype "passive"))
      (node (ref "SW1") (pin "D") (pinfunction "1_D") (pintype "passive"))
      (node (ref "SW2") (pin "B1") (pinfunction "P_B1") (pintype "passive"))
      (node (ref "SW2") (pin "B2") (pinfunction "P1_B2") (pintype "passive"))
      (node (ref "SW3") (pin "B1") (pinfunction "P_B1") (pintype "passive"))
      (node (ref "SW3") (pin "B2") (pinfunction "P1_B2") (pintype "passive"))
      (node (ref "SW4") (pin "B1") (pinfunction "P_B1") (pintype "passive"))
      (node (ref "SW4") (pin "B2") (pinfunction "P1_B2") (pintype "passive"))
      (node (ref "UC1") (pin "20") (pinfunction "PB2/BOOT1_20") (pintype "bidirectional"))
      (node (ref "UC1") (pin "23") (pinfunction "VSS_1_23") (pintype "power_in"))
      (node (ref "UC1") (pin "35") (pinfunction "VSS_2_35") (pintype "power_in"))
      (node (ref "UC1") (pin "44") (pinfunction "BOOT0_44") (pintype "input"))
      (node (ref "UC1") (pin "47") (pinfunction "VSS_3_47") (pintype "power_in"))
      (node (ref "UC1") (pin "8") (pinfunction "VSS_A_8") (pintype "power_in"))
      (node (ref "X2") (pin "2") (pinfunction "2_2") (pintype "passive"))
    )
    (net (code "24") (name "JTCK") (class "Default")
      (node (ref "JP4") (pin "4") (pinfunction "4_4") (pintype "passive"))
      (node (ref "UC1") (pin "37") (pinfunction "PA14/JTCK/SWCLK_37") (pintype "bidirectional"))
    )
    (net (code "25") (name "JTDI") (class "Default")
      (node (ref "JP4") (pin "8") (pinfunction "8_8") (pintype "passive"))
      (node (ref "UC1") (pin "38") (pinfunction "PA15/JTDI_38") (pintype "bidirectional"))
    )
    (net (code "26") (name "JTDO") (class "Default")
      (node (ref "JP4") (pin "6") (pinfunction "6_6") (pintype "passive"))
      (node (ref "UC1") (pin "39") (pinfunction "PB3/JTDO_39") (pintype "bidirectional"))
    )
    (net (code "27") (name "JTMS") (class "Default")
      (node (ref "JP4") (pin "2") (pinfunction "2_2") (pintype "passive"))
      (node (ref "UC1") (pin "34") (pinfunction "PA13/JTMS/SWDIO_34") (pintype "bidirectional"))
    )
    (net (code "28") (name "LED_1") (class "Default")
      (node (ref "R33") (pin "1") (pinfunction "1_1") (pintype "passive"))
      (node (ref "UC1") (pin "33") (pinfunction "PA12/USART1_RTS/CAN_TX/TIM1_ETR/USBDP_33") (pintype "bidirectional"))
    )
    (net (code "29") (name "LED_2") (class "Default")
      (node (ref "R36") (pin "1") (pinfunction "1_1") (pintype "passive"))
      (node (ref "UC1") (pin "32") (pinfunction "PA11/USART1_CTS/CAN_RX/TIM1_CH4/USBDM_32") (pintype "bidirectional"))
    )
    (net (code "30") (name "LED_3") (class "Default")
      (node (ref "R41") (pin "1") (pinfunction "1_1") (pintype "passive"))
      (node (ref "UC1") (pin "29") (pinfunction "PA8/USART1_CK/TIM1_CH1/MCO_29") (pintype "bidirectional"))
    )
    (net (code "31") (name "LED_4") (class "Default")
      (node (ref "R42") (pin "1") (pinfunction "1_1") (pintype "passive"))
      (node (ref "UC1") (pin "27") (pinfunction "PB14/SPI2_MISO/USART3_RTS/TIM1_CH2N_27") (pintype "input"))
    )
    (net (code "32") (name "MIDI_RX") (class "Default")
      (node (ref "OK1") (pin "6") (pinfunction "VO_6") (pintype "passive"))
      (node (ref "R37") (pin "1") (pinfunction "1_1") (pintype "passive"))
      (node (ref "UC1") (pin "31") (pinfunction "PA10/USART1_RX/TIM1_CH3_31") (pintype "bidirectional"))
    )
    (net (code "33") (name "MIDI_TX") (class "Default")
      (node (ref "R40") (pin "2") (pinfunction "2_2") (pintype "passive"))
      (node (ref "UC1") (pin "30") (pinfunction "PA9/USART1_TX/TIM1_CH2_30") (pintype "input"))
    )
    (net (code "34") (name "Net-(D1-PadA)") (class "Default")
      (node (ref "D1") (pin "A") (pinfunction "A_A") (pintype "passive"))
      (node (ref "JP2") (pin "1") (pinfunction "1_1") (pintype "passive"))
      (node (ref "JP2") (pin "2") (pinfunction "2_2") (pintype "passive"))
    )
    (net (code "35") (name "Net-(D2-PadC)") (class "Default")
      (node (ref "D2") (pin "C") (pinfunction "C_C") (pintype "passive"))
      (node (ref "JP2") (pin "10") (pinfunction "10_10") (pintype "passive"))
      (node (ref "JP2") (pin "9") (pinfunction "9_9") (pintype "passive"))
    )
    (net (code "36") (name "Net-(DISP1-A)") (class "Default")
      (node (ref "DISP1") (pin "12") (pinfunction "A_12") (pintype "passive"))
      (node (ref "R3") (pin "2") (pinfunction "2_2") (pintype "passive"))
    )
    (net (code "37") (name "Net-(DISP1-B)") (class "Default")
      (node (ref "DISP1") (pin "10") (pinfunction "B_10") (pintype "passive"))
      (node (ref "R2") (pin "2") (pinfunction "2_2") (pintype "passive"))
    )
    (net (code "38") (name "Net-(DISP1-C)") (class "Default")
      (node (ref "DISP1") (pin "9") (pinfunction "C_9") (pintype "passive"))
      (node (ref "R10") (pin "2") (pinfunction "2_2") (pintype "passive"))
    )
    (net (code "39") (name "Net-(DISP1-D)") (class "Default")
      (node (ref "DISP1") (pin "7") (pinfunction "D_7") (pintype "passive"))
      (node (ref "R11") (pin "2") (pinfunction "2_2") (pintype "passive"))
    )
    (net (code "40") (name "Net-(DISP1-E)") (class "Default")
      (node (ref "DISP1") (pin "1") (pinfunction "E_1") (pintype "passive"))
      (node (ref "R16") (pin "2") (pinfunction "2_2") (pintype "passive"))
    )
    (net (code "41") (name "Net-(DISP1-F)") (class "Default")
      (node (ref "DISP1") (pin "18") (pinfunction "F_18") (pintype "passive"))
      (node (ref "R8") (pin "2") (pinfunction "2_2") (pintype "passive"))
    )
    (net (code "42") (name "Net-(DISP1-G)") (class "Default")
      (node (ref "DISP1") (pin "17") (pinfunction "G_17") (pintype "passive"))
      (node (ref "R7") (pin "2") (pinfunction "2_2") (pintype "passive"))
    )
    (net (code "43") (name "Net-(DISP1-H)") (class "Default")
      (node (ref "DISP1") (pin "15") (pinfunction "H_15") (pintype "passive"))
      (node (ref "R6") (pin "2") (pinfunction "2_2") (pintype "passive"))
    )
    (net (code "44") (name "Net-(DISP1-J)") (class "Default")
      (node (ref "DISP1") (pin "14") (pinfunction "J_14") (pintype "passive"))
      (node (ref "R5") (pin "2") (pinfunction "2_2") (pintype "passive"))
    )
    (net (code "45") (name "Net-(DISP1-K)") (class "Default")
      (node (ref "DISP1") (pin "6") (pinfunction "K_6") (pintype "passive"))
      (node (ref "R12") (pin "2") (pinfunction "2_2") (pintype "passive"))
    )
    (net (code "46") (name "Net-(DISP1-K1)") (class "Default")
      (node (ref "DISP1") (pin "16") (pinfunction "K1_16") (pintype "passive"))
      (node (ref "Q2") (pin "C") (pinfunction "C_C") (pintype "passive"))
    )
    (net (code "47") (name "Net-(DISP1-K2)") (class "Default")
      (node (ref "DISP1") (pin "11") (pinfunction "K2_11") (pintype "passive"))
      (node (ref "Q1") (pin "C") (pinfunction "C_C") (pintype "passive"))
    )
    (net (code "48") (name "Net-(DISP1-L)") (class "Default")
      (node (ref "DISP1") (pin "5") (pinfunction "L_5") (pintype "passive"))
      (node (ref "R13") (pin "2") (pinfunction "2_2") (pintype "passive"))
    )
    (net (code "49") (name "Net-(DISP1-M)") (class "Default")
      (node (ref "DISP1") (pin "4") (pinfunction "M_4") (pintype "passive"))
      (node (ref "R14") (pin "2") (pinfunction "2_2") (pintype "passive"))
    )
    (net (code "50") (name "Net-(DISP1-N)") (class "Default")
      (node (ref "DISP1") (pin "2") (pinfunction "N_2") (pintype "passive"))
      (node (ref "R15") (pin "2") (pinfunction "2_2") (pintype "passive"))
    )
    (net (code "51") (name "Net-(DISP1-P)") (class "Default")
      (node (ref "DISP1") (pin "13") (pinfunction "P_13") (pintype "passive"))
      (node (ref "R4") (pin "2") (pinfunction "2_2") (pintype "passive"))
    )
    (net (code "52") (name "Net-(IC2A-QA)") (class "Default")
      (node (ref "IC2") (pin "15") (pinfunction "QA_15") (pintype "tri_state"))
      (node (ref "R3") (pin "1") (pinfunction "1_1") (pintype "passive"))
    )
    (net (code "53") (name "Net-(IC2A-QB)") (class "Default")
      (node (ref "IC2") (pin "1") (pinfunction "QB_1") (pintype "tri_state"))
      (node (ref "R2") (pin "1") (pinfunction "1_1") (pintype "passive"))
    )
    (net (code "54") (name "Net-(IC2A-QC)") (class "Default")
      (node (ref "IC2") (pin "2") (pinfunction "QC_2") (pintype "tri_state"))
      (node (ref "R10") (pin "1") (pinfunction "1_1") (pintype "passive"))
    )
    (net (code "55") (name "Net-(IC2A-QD)") (class "Default")
      (node (ref "IC2") (pin "3") (pinfunction "QD_3") (pintype "tri_state"))
      (node (ref "R11") (pin "1") (pinfunction "1_1") (pintype "passive"))
    )
    (net (code "56") (name "Net-(IC2A-QE)") (class "Default")
      (node (ref "IC2") (pin "4") (pinfunction "QE_4") (pintype "tri_state"))
      (node (ref "R16") (pin "1") (pinfunction "1_1") (pintype "passive"))
    )
    (net (code "57") (name "Net-(IC2A-QF)") (class "Default")
      (node (ref "IC2") (pin "5") (pinfunction "QF_5") (pintype "tri_state"))
      (node (ref "R8") (pin "1") (pinfunction "1_1") (pintype "passive"))
    )
    (net (code "58") (name "Net-(IC2A-QG)") (class "Default")
      (node (ref "IC2") (pin "6") (pinfunction "QG_6") (pintype "tri_state"))
      (node (ref "R7") (pin "1") (pinfunction "1_1") (pintype "passive"))
    )
    (net (code "59") (name "Net-(IC2A-QH)") (class "Default")
      (node (ref "IC2") (pin "7") (pinfunction "QH_7") (pintype "tri_state"))
      (node (ref "R6") (pin "1") (pinfunction "1_1") (pintype "passive"))
    )
    (net (code "60") (name "Net-(IC2A-QH*)") (class "Default")
      (node (ref "IC2") (pin "9") (pinfunction "QH*_9") (pintype "tri_state"))
      (node (ref "IC3") (pin "14") (pinfunction "SER_14") (pintype "input"))
    )
    (net (code "61") (name "Net-(IC3A-QA)") (class "Default")
      (node (ref "IC3") (pin "15") (pinfunction "QA_15") (pintype "tri_state"))
      (node (ref "R5") (pin "1") (pinfunction "1_1") (pintype "passive"))
    )
    (net (code "62") (name "Net-(IC3A-QB)") (class "Default")
      (node (ref "IC3") (pin "1") (pinfunction "QB_1") (pintype "tri_state"))
      (node (ref "R12") (pin "1") (pinfunction "1_1") (pintype "passive"))
    )
    (net (code "63") (name "Net-(IC3A-QC)") (class "Default")
      (node (ref "IC3") (pin "2") (pinfunction "QC_2") (pintype "tri_state"))
      (node (ref "R13") (pin "1") (pinfunction "1_1") (pintype "passive"))
    )
    (net (code "64") (name "Net-(IC3A-QD)") (class "Default")
      (node (ref "IC3") (pin "3") (pinfunction "QD_3") (pintype "tri_state"))
      (node (ref "R14") (pin "1") (pinfunction "1_1") (pintype "passive"))
    )
    (net (code "65") (name "Net-(IC3A-QE)") (class "Default")
      (node (ref "IC3") (pin "4") (pinfunction "QE_4") (pintype "tri_state"))
      (node (ref "R15") (pin "1") (pinfunction "1_1") (pintype "passive"))
    )
    (net (code "66") (name "Net-(IC3A-QF)") (class "Default")
      (node (ref "IC3") (pin "5") (pinfunction "QF_5") (pintype "tri_state"))
      (node (ref "R4") (pin "1") (pinfunction "1_1") (pintype "passive"))
    )
    (net (code "67") (name "Net-(IC6A--IN)") (class "Default")
      (node (ref "C14") (pin "1") (pinfunction "1_1") (pintype "passive"))
      (node (ref "IC6") (pin "2") (pinfunction "-IN_2") (pintype "input"))
      (node (ref "R18") (pin "1") (pinfunction "1_1") (pintype "passive"))
      (node (ref "R26") (pin "2") (pinfunction "2_2") (pintype "passive"))
    )
    (net (code "68") (name "Net-(IC6A-OUT)") (class "Default")
      (node (ref "C14") (pin "2") (pinfunction "2_2") (pintype "passive"))
      (node (ref "IC6") (pin "1") (pinfunction "OUT_1") (pintype "output"))
      (node (ref "R24") (pin "2") (pinfunction "2_2") (pintype "passive"))
    )
    (net (code "69") (name "Net-(IC6B--IN)") (class "Default")
      (node (ref "C21") (pin "1") (pinfunction "1_1") (pintype "passive"))
      (node (ref "IC6") (pin "6") (pinfunction "-IN_6") (pintype "input"))
      (node (ref "R19") (pin "1") (pinfunction "1_1") (pintype "passive"))
      (node (ref "R28") (pin "2") (pinfunction "2_2") (pintype "passive"))
    )
    (net (code "70") (name "Net-(IC6B-OUT)") (class "Default")
      (node (ref "C21") (pin "2") (pinfunction "2_2") (pintype "passive"))
      (node (ref "IC6") (pin "7") (pinfunction "OUT_7") (pintype "output"))
      (node (ref "R30") (pin "2") (pinfunction "2_2") (pintype "passive"))
    )
    (net (code "71") (name "Net-(IC6C--IN)") (class "Default")
      (node (ref "C22") (pin "1") (pinfunction "1_1") (pintype "passive"))
      (node (ref "IC6") (pin "9") (pinfunction "-IN_9") (pintype "input"))
      (node (ref "R20") (pin "1") (pinfunction "1_1") (pintype "passive"))
      (node (ref "R29") (pin "2") (pinfunction "2_2") (pintype "passive"))
    )
    (net (code "72") (name "Net-(IC6C-OUT)") (class "Default")
      (node (ref "C22") (pin "2") (pinfunction "2_2") (pintype "passive"))
      (node (ref "IC6") (pin "8") (pinfunction "OUT_8") (pintype "output"))
      (node (ref "R31") (pin "2") (pinfunction "2_2") (pintype "passive"))
    )
    (net (code "73") (name "Net-(IC6D--IN)") (class "Default")
      (node (ref "C16") (pin "1") (pinfunction "1_1") (pintype "passive"))
      (node (ref "IC6") (pin "13") (pinfunction "-IN_13") (pintype "input"))
      (node (ref "R21") (pin "1") (pinfunction "1_1") (pintype "passive"))
      (node (ref "R27") (pin "2") (pinfunction "2_2") (pintype "passive"))
    )
    (net (code "74") (name "Net-(IC6D-OUT)") (class "Default")
      (node (ref "C16") (pin "2") (pinfunction "2_2") (pintype "passive"))
      (node (ref "IC6") (pin "14") (pinfunction "OUT_14") (pintype "output"))
      (node (ref "R25") (pin "2") (pinfunction "2_2") (pintype "passive"))
    )
    (net (code "75") (name "Net-(IC7A-O)") (class "Default")
      (node (ref "IC7") (pin "4") (pinfunction "O_4") (pintype "tri_state"))
      (node (ref "R32") (pin "2") (pinfunction "2_2") (pintype "passive"))
    )
    (net (code "76") (name "Net-(IC8A-O)") (class "Default")
      (node (ref "IC8") (pin "4") (pinfunction "O_4") (pintype "tri_state"))
      (node (ref "R34") (pin "2") (pinfunction "2_2") (pintype "passive"))
    )
    (net (code "77") (name "Net-(IC10A-O)") (class "Default")
      (node (ref "IC10") (pin "4") (pinfunction "O_4") (pintype "tri_state"))
      (node (ref "R38") (pin "2") (pinfunction "2_2") (pintype "passive"))
    )
    (net (code "78") (name "Net-(IC11A-O)") (class "Default")
      (node (ref "IC11") (pin "4") (pinfunction "O_4") (pintype "tri_state"))
      (node (ref "R43") (pin "2") (pinfunction "2_2") (pintype "passive"))
    )
    (net (code "79") (name "Net-(J1-2)") (class "Default")
      (node (ref "J1") (pin "TIP") (pinfunction "2_TIP") (pintype "passive"))
      (node (ref "R25") (pin "1") (pinfunction "1_1") (pintype "passive"))
      (node (ref "R27") (pin "1") (pinfunction "1_1") (pintype "passive"))
    )
    (net (code "80") (name "Net-(J2-2)") (class "Default")
      (node (ref "J2") (pin "TIP") (pinfunction "2_TIP") (pintype "passive"))
      (node (ref "R32") (pin "1") (pinfunction "1_1") (pintype "passive"))
    )
    (net (code "81") (name "Net-(J3-2)") (class "Default")
      (node (ref "J3") (pin "TIP") (pinfunction "2_TIP") (pintype "passive"))
      (node (ref "R29") (pin "1") (pinfunction "1_1") (pintype "passive"))
      (node (ref "R31") (pin "1") (pinfunction "1_1") (pintype "passive"))
    )
    (net (code "82") (name "Net-(J4-2)") (class "Default")
      (node (ref "J4") (pin "TIP") (pinfunction "2_TIP") (pintype "passive"))
      (node (ref "R34") (pin "1") (pinfunction "1_1") (pintype "passive"))
    )
    (net (code "83") (name "Net-(J5-2)") (class "Default")
      (node (ref "J5") (pin "TIP") (pinfunction "2_TIP") (pintype "passive"))
      (node (ref "R28") (pin "1") (pinfunction "1_1") (pintype "passive"))
      (node (ref "R30") (pin "1") (pinfunction "1_1") (pintype "passive"))
    )
    (net (code "84") (name "Net-(J6-2)") (class "Default")
      (node (ref "J6") (pin "TIP") (pinfunction "2_TIP") (pintype "passive"))
      (node (ref "R38") (pin "1") (pinfunction "1_1") (pintype "passive"))
    )
    (net (code "85") (name "Net-(J7-2)") (class "Default")
      (node (ref "J7") (pin "TIP") (pinfunction "2_TIP") (pintype "passive"))
      (node (ref "R24") (pin "1") (pinfunction "1_1") (pintype "passive"))
      (node (ref "R26") (pin "1") (pinfunction "1_1") (pintype "passive"))
    )
    (net (code "86") (name "Net-(J8-2)") (class "Default")
      (node (ref "J8") (pin "TIP") (pinfunction "2_TIP") (pintype "passive"))
      (node (ref "R43") (pin "1") (pinfunction "1_1") (pintype "passive"))
    )
    (net (code "87") (name "Net-(LED1-PadA)") (class "Default")
      (node (ref "LED1") (pin "A") (pinfunction "A_A") (pintype "passive"))
      (node (ref "R33") (pin "2") (pinfunction "2_2") (pintype "passive"))
    )
    (net (code "88") (name "Net-(LED2-PadA)") (class "Default")
      (node (ref "LED2") (pin "A") (pinfunction "A_A") (pintype "passive"))
      (node (ref "R36") (pin "2") (pinfunction "2_2") (pintype "passive"))
    )
    (net (code "89") (name "Net-(LED3-PadA)") (class "Default")
      (node (ref "LED3") (pin "A") (pinfunction "A_A") (pintype "passive"))
      (node (ref "R41") (pin "2") (pinfunction "2_2") (pintype "passive"))
    )
    (net (code "90") (name "Net-(LED4-PadA)") (class "Default")
      (node (ref "LED4") (pin "A") (pinfunction "A_A") (pintype "passive"))
      (node (ref "R42") (pin "2") (pinfunction "2_2") (pintype "passive"))
    )
    (net (code "91") (name "Net-(OK1-A)") (class "Default")
      (node (ref "D3") (pin "C") (pinfunction "C_C") (pintype "passive"))
      (node (ref "OK1") (pin "2") (pinfunction "A_2") (pintype "passive"))
      (node (ref "R35") (pin "1") (pinfunction "1_1") (pintype "passive"))
    )
    (net (code "92") (name "Net-(OK1-C)") (class "Default")
      (node (ref "D3") (pin "A") (pinfunction "A_A") (pintype "passive"))
      (node (ref "OK1") (pin "3") (pinfunction "C_3") (pintype "passive"))
      (node (ref "X1") (pin "5") (pinfunction "5_5") (pintype "passive"))
    )
    (net (code "93") (name "Net-(Q1-PadB)") (class "Default")
      (node (ref "Q1") (pin "B") (pinfunction "B_B") (pintype "passive"))
      (node (ref "R1") (pin "2") (pinfunction "2_2") (pintype "passive"))
    )
    (net (code "94") (name "Net-(Q2-PadB)") (class "Default")
      (node (ref "Q2") (pin "B") (pinfunction "B_B") (pintype "passive"))
      (node (ref "R9") (pin "2") (pinfunction "2_2") (pintype "passive"))
    )
    (net (code "95") (name "Net-(R35-Pad2)") (class "Default")
      (node (ref "R35") (pin "2") (pinfunction "2_2") (pintype "passive"))
      (node (ref "X1") (pin "4") (pinfunction "4_4") (pintype "passive"))
    )
    (net (code "96") (name "Net-(R39-Pad1)") (class "Default")
      (node (ref "R39") (pin "1") (pinfunction "1_1") (pintype "passive"))
      (node (ref "X2") (pin "4") (pinfunction "4_4") (pintype "passive"))
    )
    (net (code "97") (name "Net-(R40-Pad1)") (class "Default")
      (node (ref "R40") (pin "1") (pinfunction "1_1") (pintype "passive"))
      (node (ref "X2") (pin "5") (pinfunction "5_5") (pintype "passive"))
    )
    (net (code "98") (name "Net-(UC1-PD0-OSC_IN)") (class "Default")
      (node (ref "C7") (pin "2") (pinfunction "2_2") (pintype "passive"))
      (node (ref "Q3") (pin "2") (pinfunction "2_2") (pintype "passive"))
      (node (ref "UC1") (pin "5") (pinfunction "PD0-OSC_IN_5") (pintype "input"))
    )
    (net (code "99") (name "Net-(UC1-PD1-OSC_OUT)") (class "Default")
      (node (ref "C10") (pin "2") (pinfunction "2_2") (pintype "passive"))
      (node (ref "Q3") (pin "1") (pinfunction "1_1") (pintype "passive"))
      (node (ref "UC1") (pin "6") (pinfunction "PD1-OSC_OUT_6") (pintype "input"))
    )
    (net (code "100") (name "RESET") (class "Default")
      (node (ref "JP4") (pin "10") (pinfunction "10_10") (pintype "passive"))
      (node (ref "R17") (pin "1") (pinfunction "1_1") (pintype "passive"))
      (node (ref "UC1") (pin "7") (pinfunction "NRST_7") (pintype "input"))
    )
    (net (code "101") (name "SWITCH_0") (class "Default")
      (node (ref "SW2") (pin "A1") (pinfunction "S_A1") (pintype "passive"))
      (node (ref "SW2") (pin "A2") (pinfunction "S1_A2") (pintype "passive"))
      (node (ref "UC1") (pin "15") (pinfunction "PA5/SPI1_SCK/ADC12_IN5_15") (pintype "bidirectional"))
    )
    (net (code "102") (name "SWITCH_1") (class "Default")
      (node (ref "SW3") (pin "A1") (pinfunction "S_A1") (pintype "passive"))
      (node (ref "SW3") (pin "A2") (pinfunction "S1_A2") (pintype "passive"))
      (node (ref "UC1") (pin "16") (pinfunction "PA6/SPI1_MISO/ADC12_IN6/TIM3_CH1_16") (pintype "bidirectional"))
    )
    (net (code "103") (name "SWITCH_2") (class "Default")
      (node (ref "SW4") (pin "A1") (pinfunction "S_A1") (pintype "passive"))
      (node (ref "SW4") (pin "A2") (pinfunction "S1_A2") (pintype "passive"))
      (node (ref "UC1") (pin "14") (pinfunction "PA4/SPI1_NSS/USART2_CK/ADC12_IN4_14") (pintype "bidirectional"))
    )
    (net (code "104") (name "VCC") (class "Default")
      (node (ref "C1") (pin "+") (pinfunction "+_+") (pintype "passive"))
      (node (ref "C12") (pin "+") (pinfunction "+_+") (pintype "passive"))
      (node (ref "C19") (pin "1") (pinfunction "1_1") (pintype "passive"))
      (node (ref "C25") (pin "1") (pinfunction "1_1") (pintype "passive"))
      (node (ref "D1") (pin "C") (pinfunction "C_C") (pintype "passive"))
      (node (ref "IC1") (pin "3") (pinfunction "VIN_3") (pintype "input"))
      (node (ref "IC5") (pin "2") (pinfunction "V+_2") (pintype "power_in"))
      (node (ref "IC6") (pin "4") (pinfunction "V+_4") (pintype "power_in"))
      (node (ref "IC9") (pin "3") (pinfunction "VI_3") (pintype "input"))
    )
    (net (code "105") (name "VEE") (class "Default")
      (node (ref "C20") (pin "2") (pinfunction "2_2") (pintype "passive"))
      (node (ref "C3") (pin "-") (pinfunction "-_-") (pintype "passive"))
      (node (ref "D2") (pin "A") (pinfunction "A_A") (pintype "passive"))
      (node (ref "IC6") (pin "11") (pinfunction "V-_11") (pintype "power_in"))
    )
    (net (code "106") (name "VREF") (class "Default")
      (node (ref "C17") (pin "1") (pinfunction "1_1") (pintype "passive"))
      (node (ref "IC4") (pin "3") (pinfunction "VREFH_3") (pintype "bidirectional"))
      (node (ref "R23") (pin "2") (pinfunction "2_2") (pintype "passive"))
    )
    (net (code "107") (name "VREF{slash}2") (class "Default")
      (node (ref "IC6") (pin "10") (pinfunction "+IN_10") (pintype "input"))
      (node (ref "IC6") (pin "12") (pinfunction "+IN_12") (pintype "input"))
      (node (ref "IC6") (pin "3") (pinfunction "+IN_3") (pintype "input"))
      (node (ref "IC6") (pin "5") (pinfunction "+IN_5") (pintype "input"))
      (node (ref "R22") (pin "2") (pinfunction "2_2") (pintype "passive"))
      (node (ref "R23") (pin "1") (pinfunction "1_1") (pintype "passive"))
    )
    (net (code "108") (name "unconnected-(DISP1-DP-Pad8)") (class "Default")
      (node (ref "DISP1") (pin "8") (pinfunction "DP_8") (pintype "passive"))
    )
    (net (code "109") (name "unconnected-(IC3A-QG-Pad6)") (class "Default")
      (node (ref "IC3") (pin "6") (pinfunction "QG_6") (pintype "tri_state"))
    )
    (net (code "110") (name "unconnected-(IC3A-QH*-Pad9)") (class "Default")
      (node (ref "IC3") (pin "9") (pinfunction "QH*_9") (pintype "tri_state"))
    )
    (net (code "111") (name "unconnected-(IC3A-QH-Pad7)") (class "Default")
      (node (ref "IC3") (pin "7") (pinfunction "QH_7") (pintype "tri_state"))
    )
    (net (code "112") (name "unconnected-(IC5-OPT-Pad3)") (class "Default")
      (node (ref "IC5") (pin "3") (pinfunction "OPT_3") (pintype "output"))
    )
    (net (code "113") (name "unconnected-(IC5-TRM-Pad5)") (class "Default")
      (node (ref "IC5") (pin "5") (pinfunction "TRM_5") (pintype "input"))
    )
    (net (code "114") (name "unconnected-(J1-3-PadSW)") (class "Default")
      (node (ref "J1") (pin "SW") (pinfunction "3_SW") (pintype "passive"))
    )
    (net (code "115") (name "unconnected-(J2-3-PadSW)") (class "Default")
      (node (ref "J2") (pin "SW") (pinfunction "3_SW") (pintype "passive"))
    )
    (net (code "116") (name "unconnected-(J3-3-PadSW)") (class "Default")
      (node (ref "J3") (pin "SW") (pinfunction "3_SW") (pintype "passive"))
    )
    (net (code "117") (name "unconnected-(J4-3-PadSW)") (class "Default")
      (node (ref "J4") (pin "SW") (pinfunction "3_SW") (pintype "passive"))
    )
    (net (code "118") (name "unconnected-(J5-3-PadSW)") (class "Default")
      (node (ref "J5") (pin "SW") (pinfunction "3_SW") (pintype "passive"))
    )
    (net (code "119") (name "unconnected-(J6-3-PadSW)") (class "Default")
      (node (ref "J6") (pin "SW") (pinfunction "3_SW") (pintype "passive"))
    )
    (net (code "120") (name "unconnected-(J7-3-PadSW)") (class "Default")
      (node (ref "J7") (pin "SW") (pinfunction "3_SW") (pintype "passive"))
    )
    (net (code "121") (name "unconnected-(J8-3-PadSW)") (class "Default")
      (node (ref "J8") (pin "SW") (pinfunction "3_SW") (pintype "passive"))
    )
    (net (code "122") (name "unconnected-(JP4-Pad7)") (class "Default")
      (node (ref "JP4") (pin "7") (pinfunction "7_7") (pintype "passive"))
    )
    (net (code "123") (name "unconnected-(OK1-VE-Pad7)") (class "Default")
      (node (ref "OK1") (pin "7") (pinfunction "VE_7") (pintype "passive"))
    )
    (net (code "124") (name "unconnected-(UC1-PA0_WKUP{slash}USART2_CTS{slash}ADC12_IN0{slash}TIM2_CH1_ETR-Pad10)") (class "Default")
      (node (ref "UC1") (pin "10") (pinfunction "PA0_WKUP/USART2_CTS/ADC12_IN0/TIM2_CH1_ETR_10") (pintype "bidirectional"))
    )
    (net (code "125") (name "unconnected-(UC1-PA1{slash}USART2_RTS{slash}ADC12_IN1{slash}TIM2_CH2-Pad11)") (class "Default")
      (node (ref "UC1") (pin "11") (pinfunction "PA1/USART2_RTS/ADC12_IN1/TIM2_CH2_11") (pintype "bidirectional"))
    )
    (net (code "126") (name "unconnected-(UC1-PA2{slash}USART2_TX{slash}ADC12_IN2{slash}TIM2_CH3-Pad12)") (class "Default")
      (node (ref "UC1") (pin "12") (pinfunction "PA2/USART2_TX/ADC12_IN2/TIM2_CH3_12") (pintype "bidirectional"))
    )
    (net (code "127") (name "unconnected-(UC1-PA3{slash}USART2_RX{slash}ADC12_IN3{slash}TIM2_CH4-Pad13)") (class "Default")
      (node (ref "UC1") (pin "13") (pinfunction "PA3/USART2_RX/ADC12_IN3/TIM2_CH4_13") (pintype "bidirectional"))
    )
    (net (code "128") (name "unconnected-(UC1-PA7{slash}SPI1_MOSI{slash}ADC12_IN7{slash}TIM3_CH2-Pad17)") (class "Default")
      (node (ref "UC1") (pin "17") (pinfunction "PA7/SPI1_MOSI/ADC12_IN7/TIM3_CH2_17") (pintype "bidirectional"))
    )
    (net (code "129") (name "unconnected-(UC1-PB4{slash}NJTRST-Pad40)") (class "Default")
      (node (ref "UC1") (pin "40") (pinfunction "PB4/NJTRST_40") (pintype "bidirectional"))
    )
    (net (code "130") (name "unconnected-(X1-Pad1)") (class "Default")
      (node (ref "X1") (pin "1") (pinfunction "1_1") (pintype "passive"))
    )
    (net (code "131") (name "unconnected-(X1-Pad2)") (class "Default")
      (node (ref "X1") (pin "2") (pinfunction "2_2") (pintype "passive"))
    )
    (net (code "132") (name "unconnected-(X1-Pad3)") (class "Default")
      (node (ref "X1") (pin "3") (pinfunction "3_3") (pintype "passive"))
    )
    (net (code "133") (name "unconnected-(X2-Pad1)") (class "Default")
      (node (ref "X2") (pin "1") (pinfunction "1_1") (pintype "passive"))
    )
    (net (code "134") (name "unconnected-(X2-Pad3)") (class "Default")
      (node (ref "X2") (pin "3") (pinfunction "3_3") (pintype "passive"))
    )
  )
)
